# DOAN1.net
KiCad netlist of a schematic drawn in EasyEDA
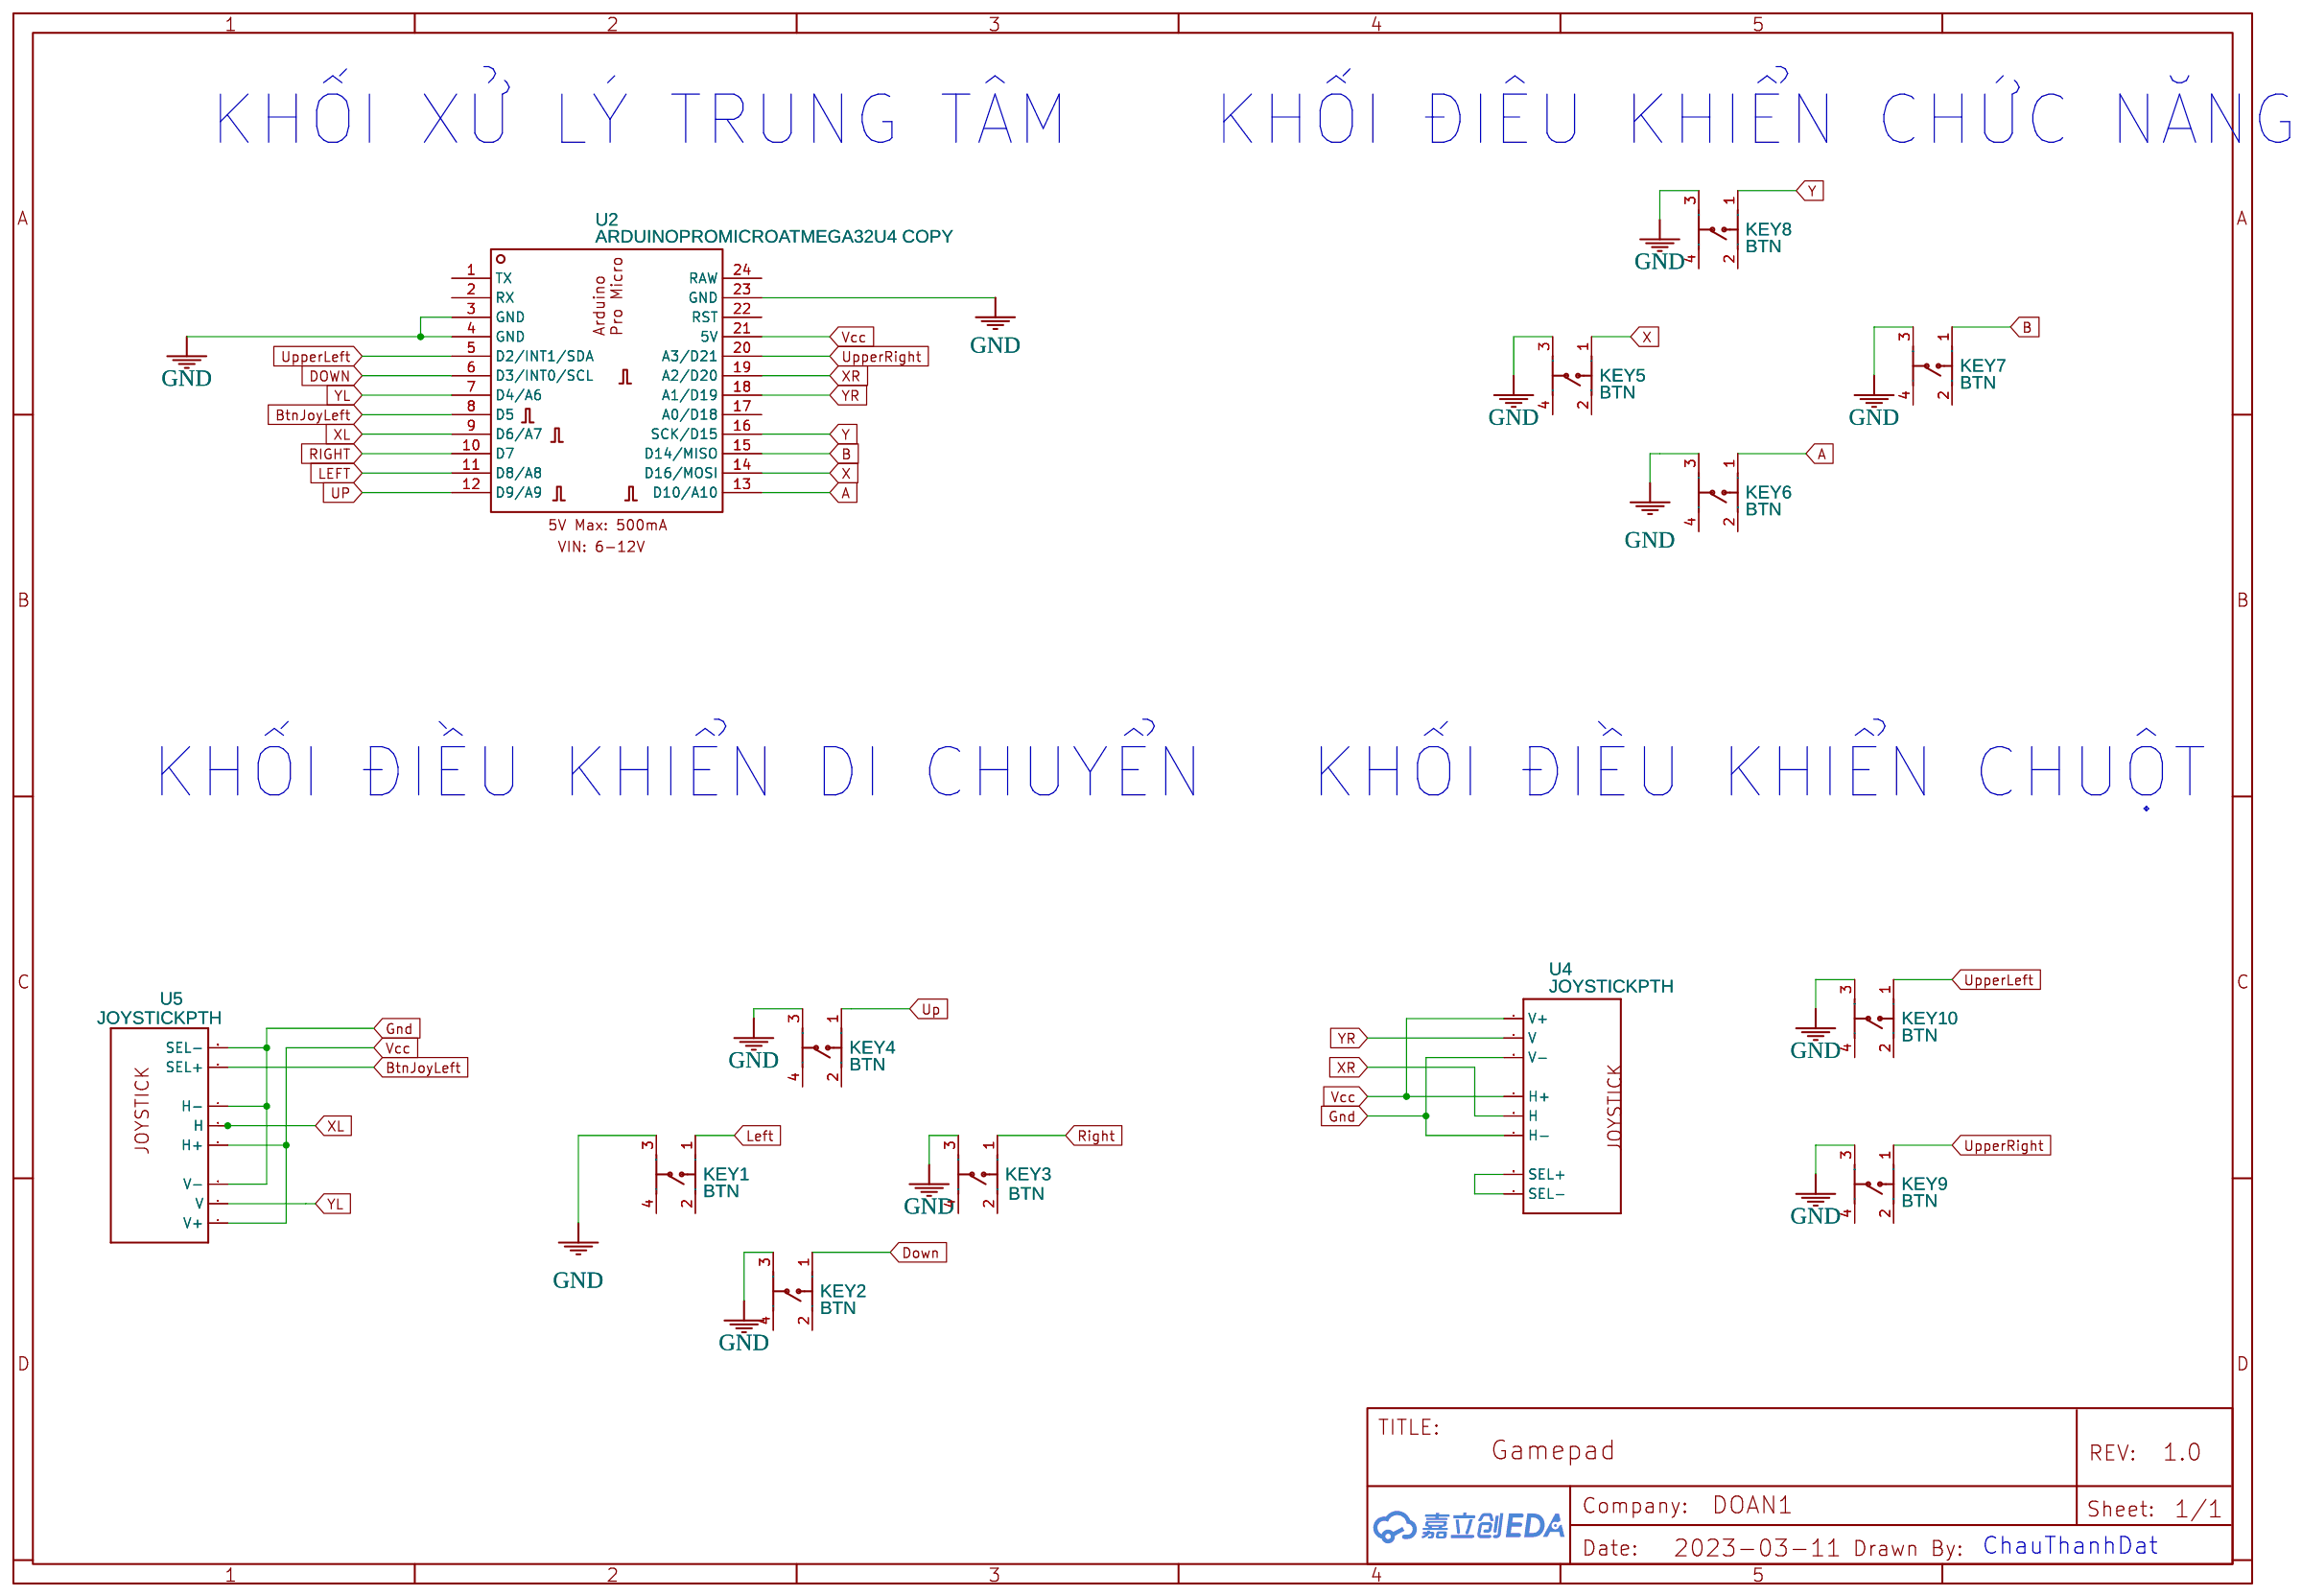
[diagram p0: schematic sheet]

(export (version "E")
  (design (tool "Eeschema 10.0.6"))
  (components
    (comp (ref "KEY1")
      (value "BTN")
      (fields
        (field (name "BOM_Manufacturer Part") "4pinTACTPCBTHTPushButton")
        (field (name "BOM_Supplier Part") "C9900003768")
      )
      (libsource (lib "") (part "4PINTACTPCBTHTPUSHBUTTON"))
    )
    (comp (ref "KEY2")
      (value "BTN")
      (fields
        (field (name "BOM_Manufacturer Part") "4pinTACTPCBTHTPushButton")
        (field (name "BOM_Supplier Part") "C9900003768")
      )
      (libsource (lib "") (part "4PINTACTPCBTHTPUSHBUTTON"))
    )
    (comp (ref "KEY3")
      (value "BTN")
      (fields
        (field (name "BOM_Manufacturer Part") "4pinTACTPCBTHTPushButton")
        (field (name "BOM_Supplier Part") "C9900003768")
      )
      (libsource (lib "") (part "4PINTACTPCBTHTPUSHBUTTON"))
    )
    (comp (ref "KEY4")
      (value "BTN")
      (fields
        (field (name "BOM_Manufacturer Part") "4pinTACTPCBTHTPushButton")
        (field (name "BOM_Supplier Part") "C9900003768")
      )
      (libsource (lib "") (part "4PINTACTPCBTHTPUSHBUTTON"))
    )
    (comp (ref "KEY5")
      (value "BTN")
      (fields
        (field (name "BOM_Manufacturer Part") "4pinTACTPCBTHTPushButton")
        (field (name "BOM_Supplier Part") "C9900003768")
      )
      (libsource (lib "") (part "4PINTACTPCBTHTPUSHBUTTON"))
    )
    (comp (ref "KEY6")
      (value "BTN")
      (fields
        (field (name "BOM_Manufacturer Part") "4pinTACTPCBTHTPushButton")
        (field (name "BOM_Supplier Part") "C9900003768")
      )
      (libsource (lib "") (part "4PINTACTPCBTHTPUSHBUTTON"))
    )
    (comp (ref "KEY7")
      (value "BTN")
      (fields
        (field (name "BOM_Manufacturer Part") "4pinTACTPCBTHTPushButton")
        (field (name "BOM_Supplier Part") "C9900003768")
      )
      (libsource (lib "") (part "4PINTACTPCBTHTPUSHBUTTON"))
    )
    (comp (ref "KEY8")
      (value "BTN")
      (fields
        (field (name "BOM_Manufacturer Part") "4pinTACTPCBTHTPushButton")
        (field (name "BOM_Supplier Part") "C9900003768")
      )
      (libsource (lib "") (part "4PINTACTPCBTHTPUSHBUTTON"))
    )
    (comp (ref "KEY9")
      (value "BTN")
      (fields
        (field (name "BOM_Manufacturer Part") "4pinTACTPCBTHTPushButton")
        (field (name "BOM_Supplier Part") "C9900003768")
      )
      (libsource (lib "") (part "4PINTACTPCBTHTPUSHBUTTON"))
    )
    (comp (ref "KEY10")
      (value "BTN")
      (fields
        (field (name "BOM_Manufacturer Part") "4pinTACTPCBTHTPushButton")
        (field (name "BOM_Supplier Part") "C9900003768")
      )
      (libsource (lib "") (part "4PINTACTPCBTHTPUSHBUTTON"))
    )
    (comp (ref "U2")
      (value "ARDUINOPROMICROATMEGA32U4 COPY")
      (libsource (lib "") (part "ARDUINOPROMICROATMEGA32U4 COPY"))
    )
    (comp (ref "U4") (value "JOYSTICKPTH") (libsource (lib "") (part "JOYSTICKPTH")))
    (comp (ref "U5") (value "JOYSTICKPTH") (libsource (lib "") (part "JOYSTICKPTH_1")))
  )
  (nets
    (net (code "1") (name "A") (class "Default")
      (node (ref "KEY6") (pin "1") (pinfunction "1_1") (pintype "unspecified"))
      (node (ref "U2") (pin "13") (pinfunction "D10/A10_13") (pintype "unspecified"))
    )
    (net (code "2") (name "B") (class "Default")
      (node (ref "KEY7") (pin "1") (pinfunction "1_1") (pintype "unspecified"))
      (node (ref "U2") (pin "15") (pinfunction "D14/MISO_15") (pintype "unspecified"))
    )
    (net (code "3") (name "BtnJoyLeft") (class "Default")
      (node (ref "U2") (pin "8") (pinfunction "D5_8") (pintype "unspecified"))
      (node (ref "U5") (pin "B1A") (pinfunction "SEL+_B1A") (pintype "unspecified"))
    )
    (net (code "4") (name "DOWN") (class "Default")
      (node (ref "U2") (pin "6") (pinfunction "D3/INT0/SCL_6") (pintype "unspecified"))
    )
    (net (code "5") (name "Down") (class "Default")
      (node (ref "KEY2") (pin "1") (pinfunction "1_1") (pintype "unspecified"))
    )
    (net (code "6") (name "GND") (class "Default")
      (node (ref "KEY1") (pin "3") (pinfunction "3_3") (pintype "unspecified"))
      (node (ref "KEY10") (pin "3") (pinfunction "3_3") (pintype "unspecified"))
      (node (ref "KEY2") (pin "3") (pinfunction "3_3") (pintype "unspecified"))
      (node (ref "KEY3") (pin "3") (pinfunction "3_3") (pintype "unspecified"))
      (node (ref "KEY4") (pin "3") (pinfunction "3_3") (pintype "unspecified"))
      (node (ref "KEY5") (pin "3") (pinfunction "3_3") (pintype "unspecified"))
      (node (ref "KEY6") (pin "3") (pinfunction "3_3") (pintype "unspecified"))
      (node (ref "KEY7") (pin "3") (pinfunction "3_3") (pintype "unspecified"))
      (node (ref "KEY8") (pin "3") (pinfunction "3_3") (pintype "unspecified"))
      (node (ref "KEY9") (pin "3") (pinfunction "3_3") (pintype "unspecified"))
      (node (ref "U2") (pin "23") (pinfunction "GND_23") (pintype "unspecified"))
      (node (ref "U2") (pin "3") (pinfunction "GND_3") (pintype "unspecified"))
      (node (ref "U2") (pin "4") (pinfunction "GND_4") (pintype "unspecified"))
    )
    (net (code "7") (name "Gnd") (class "Default")
      (node (ref "U4") (pin "H3") (pinfunction "H-_H3") (pintype "unspecified"))
      (node (ref "U4") (pin "V3") (pinfunction "V-_V3") (pintype "unspecified"))
      (node (ref "U5") (pin "B2A") (pinfunction "SEL-_B2A") (pintype "unspecified"))
      (node (ref "U5") (pin "H3") (pinfunction "H-_H3") (pintype "unspecified"))
      (node (ref "U5") (pin "V3") (pinfunction "V-_V3") (pintype "unspecified"))
    )
    (net (code "8") (name "LEFT") (class "Default")
      (node (ref "U2") (pin "11") (pinfunction "D8/A8_11") (pintype "unspecified"))
    )
    (net (code "9") (name "Left") (class "Default")
      (node (ref "KEY1") (pin "1") (pinfunction "1_1") (pintype "unspecified"))
    )
    (net (code "10") (name "Net-(U4-SEL+)") (class "Default")
      (node (ref "U4") (pin "B1A") (pinfunction "SEL+_B1A") (pintype "unspecified"))
      (node (ref "U4") (pin "B2A") (pinfunction "SEL-_B2A") (pintype "unspecified"))
    )
    (net (code "11") (name "RIGHT") (class "Default")
      (node (ref "U2") (pin "10") (pinfunction "D7_10") (pintype "unspecified"))
    )
    (net (code "12") (name "Right") (class "Default")
      (node (ref "KEY3") (pin "1") (pinfunction "1_1") (pintype "unspecified"))
    )
    (net (code "13") (name "UP") (class "Default")
      (node (ref "U2") (pin "12") (pinfunction "D9/A9_12") (pintype "unspecified"))
    )
    (net (code "14") (name "Up") (class "Default")
      (node (ref "KEY4") (pin "1") (pinfunction "1_1") (pintype "unspecified"))
    )
    (net (code "15") (name "UpperLeft") (class "Default")
      (node (ref "KEY10") (pin "1") (pinfunction "1_1") (pintype "unspecified"))
      (node (ref "U2") (pin "5") (pinfunction "D2/INT1/SDA_5") (pintype "unspecified"))
    )
    (net (code "16") (name "UpperRight") (class "Default")
      (node (ref "KEY9") (pin "1") (pinfunction "1_1") (pintype "unspecified"))
      (node (ref "U2") (pin "20") (pinfunction "A3/D21_20") (pintype "unspecified"))
    )
    (net (code "17") (name "Vcc") (class "Default")
      (node (ref "U2") (pin "21") (pinfunction "5V_21") (pintype "unspecified"))
      (node (ref "U4") (pin "H1") (pinfunction "H+_H1") (pintype "unspecified"))
      (node (ref "U4") (pin "V1") (pinfunction "V+_V1") (pintype "unspecified"))
      (node (ref "U5") (pin "H1") (pinfunction "H+_H1") (pintype "unspecified"))
      (node (ref "U5") (pin "V1") (pinfunction "V+_V1") (pintype "unspecified"))
    )
    (net (code "18") (name "X") (class "Default")
      (node (ref "KEY5") (pin "1") (pinfunction "1_1") (pintype "unspecified"))
      (node (ref "U2") (pin "14") (pinfunction "D16/MOSI_14") (pintype "unspecified"))
    )
    (net (code "19") (name "XL") (class "Default")
      (node (ref "U2") (pin "9") (pinfunction "D6/A7_9") (pintype "unspecified"))
      (node (ref "U5") (pin "H2") (pinfunction "H_H2") (pintype "unspecified"))
    )
    (net (code "20") (name "XR") (class "Default")
      (node (ref "U2") (pin "19") (pinfunction "A2/D20_19") (pintype "unspecified"))
      (node (ref "U4") (pin "H2") (pinfunction "H_H2") (pintype "unspecified"))
    )
    (net (code "21") (name "Y") (class "Default")
      (node (ref "KEY8") (pin "1") (pinfunction "1_1") (pintype "unspecified"))
      (node (ref "U2") (pin "16") (pinfunction "SCK/D15_16") (pintype "unspecified"))
    )
    (net (code "22") (name "YL") (class "Default")
      (node (ref "U2") (pin "7") (pinfunction "D4/A6_7") (pintype "unspecified"))
      (node (ref "U5") (pin "V2") (pinfunction "V_V2") (pintype "unspecified"))
    )
    (net (code "23") (name "YR") (class "Default")
      (node (ref "U2") (pin "18") (pinfunction "A1/D19_18") (pintype "unspecified"))
      (node (ref "U4") (pin "V2") (pinfunction "V_V2") (pintype "unspecified"))
    )
    (net (code "24") (name "unconnected-(KEY1-Pad2)") (class "Default")
      (node (ref "KEY1") (pin "2") (pinfunction "2_2") (pintype "unspecified"))
    )
    (net (code "25") (name "unconnected-(KEY1-Pad4)") (class "Default")
      (node (ref "KEY1") (pin "4") (pinfunction "4_4") (pintype "unspecified"))
    )
    (net (code "26") (name "unconnected-(KEY2-Pad2)") (class "Default")
      (node (ref "KEY2") (pin "2") (pinfunction "2_2") (pintype "unspecified"))
    )
    (net (code "27") (name "unconnected-(KEY2-Pad4)") (class "Default")
      (node (ref "KEY2") (pin "4") (pinfunction "4_4") (pintype "unspecified"))
    )
    (net (code "28") (name "unconnected-(KEY3-Pad2)") (class "Default")
      (node (ref "KEY3") (pin "2") (pinfunction "2_2") (pintype "unspecified"))
    )
    (net (code "29") (name "unconnected-(KEY3-Pad4)") (class "Default")
      (node (ref "KEY3") (pin "4") (pinfunction "4_4") (pintype "unspecified"))
    )
    (net (code "30") (name "unconnected-(KEY4-Pad2)") (class "Default")
      (node (ref "KEY4") (pin "2") (pinfunction "2_2") (pintype "unspecified"))
    )
    (net (code "31") (name "unconnected-(KEY4-Pad4)") (class "Default")
      (node (ref "KEY4") (pin "4") (pinfunction "4_4") (pintype "unspecified"))
    )
    (net (code "32") (name "unconnected-(KEY5-Pad2)") (class "Default")
      (node (ref "KEY5") (pin "2") (pinfunction "2_2") (pintype "unspecified"))
    )
    (net (code "33") (name "unconnected-(KEY5-Pad4)") (class "Default")
      (node (ref "KEY5") (pin "4") (pinfunction "4_4") (pintype "unspecified"))
    )
    (net (code "34") (name "unconnected-(KEY6-Pad2)") (class "Default")
      (node (ref "KEY6") (pin "2") (pinfunction "2_2") (pintype "unspecified"))
    )
    (net (code "35") (name "unconnected-(KEY6-Pad4)") (class "Default")
      (node (ref "KEY6") (pin "4") (pinfunction "4_4") (pintype "unspecified"))
    )
    (net (code "36") (name "unconnected-(KEY7-Pad2)") (class "Default")
      (node (ref "KEY7") (pin "2") (pinfunction "2_2") (pintype "unspecified"))
    )
    (net (code "37") (name "unconnected-(KEY7-Pad4)") (class "Default")
      (node (ref "KEY7") (pin "4") (pinfunction "4_4") (pintype "unspecified"))
    )
    (net (code "38") (name "unconnected-(KEY8-Pad2)") (class "Default")
      (node (ref "KEY8") (pin "2") (pinfunction "2_2") (pintype "unspecified"))
    )
    (net (code "39") (name "unconnected-(KEY8-Pad4)") (class "Default")
      (node (ref "KEY8") (pin "4") (pinfunction "4_4") (pintype "unspecified"))
    )
    (net (code "40") (name "unconnected-(KEY9-Pad2)") (class "Default")
      (node (ref "KEY9") (pin "2") (pinfunction "2_2") (pintype "unspecified"))
    )
    (net (code "41") (name "unconnected-(KEY9-Pad4)") (class "Default")
      (node (ref "KEY9") (pin "4") (pinfunction "4_4") (pintype "unspecified"))
    )
    (net (code "42") (name "unconnected-(KEY10-Pad2)") (class "Default")
      (node (ref "KEY10") (pin "2") (pinfunction "2_2") (pintype "unspecified"))
    )
    (net (code "43") (name "unconnected-(KEY10-Pad4)") (class "Default")
      (node (ref "KEY10") (pin "4") (pinfunction "4_4") (pintype "unspecified"))
    )
    (net (code "44") (name "unconnected-(U2-A0{slash}D18-Pad17)") (class "Default")
      (node (ref "U2") (pin "17") (pinfunction "A0/D18_17") (pintype "unspecified"))
    )
    (net (code "45") (name "unconnected-(U2-RAW-Pad24)") (class "Default")
      (node (ref "U2") (pin "24") (pinfunction "RAW_24") (pintype "unspecified"))
    )
    (net (code "46") (name "unconnected-(U2-RST-Pad22)") (class "Default")
      (node (ref "U2") (pin "22") (pinfunction "RST_22") (pintype "unspecified"))
    )
    (net (code "47") (name "unconnected-(U2-RX-Pad2)") (class "Default")
      (node (ref "U2") (pin "2") (pinfunction "RX_2") (pintype "unspecified"))
    )
    (net (code "48") (name "unconnected-(U2-TX-Pad1)") (class "Default")
      (node (ref "U2") (pin "1") (pinfunction "TX_1") (pintype "unspecified"))
    )
  )
)
